# unoshield-v3.net
KiCad netlist of a schematic drawn in EAGLE
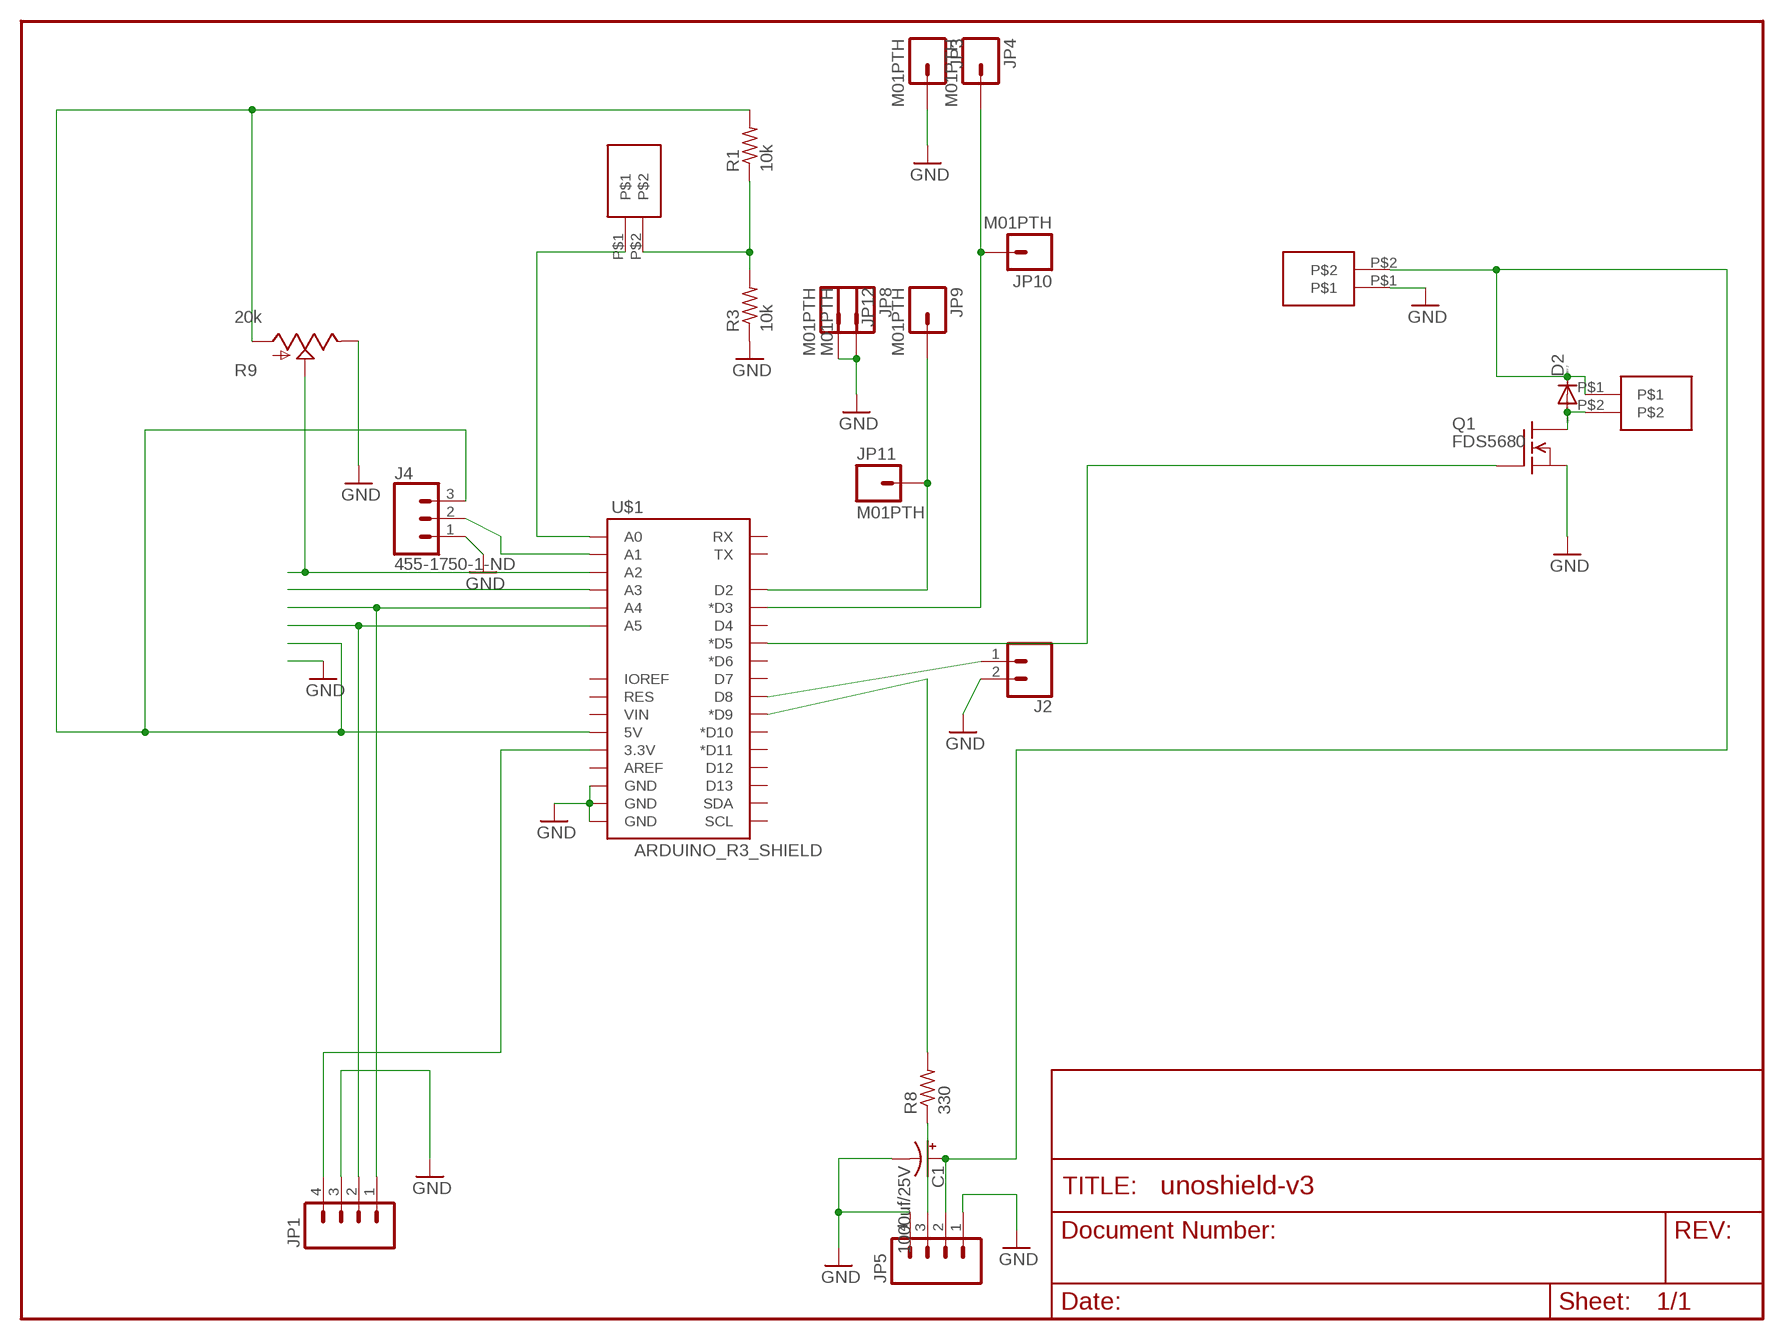
[diagram p0: schematic, sheet 1]

(export (version "E")
  (design (tool "Eeschema 10.0.6"))
  (components
    (comp (ref "C1")
      (value "1000uf/25V")
      (footprint "eagle-import:CPOL-RADIAL-1000UF-25V-KIT")
      (libsource (lib "eagle-import") (part "1000UF-25V(PTH)KIT"))
    )
    (comp (ref "D2")
      (value "DIODE-DO-214AC")
      (footprint "eagle-import:DO-214AC")
      (libsource (lib "eagle-import") (part "DIODE-DO-214AC"))
    )
    (comp (ref "J2")
      (value "CONN_02")
      (footprint "eagle-import:1X02")
      (libsource (lib "eagle-import") (part "CONN_02"))
    )
    (comp (ref "J4")
      (value "455-1750-1-ND")
      (footprint "eagle-import:1X03")
      (libsource (lib "eagle-import") (part "CONN_03"))
    )
    (comp (ref "JP1")
      (value "M04PTH")
      (footprint "eagle-import:1X04")
      (libsource (lib "eagle-import") (part "M04PTH"))
    )
    (comp (ref "JP3")
      (value "M01PTH")
      (footprint "eagle-import:1X01")
      (libsource (lib "eagle-import") (part "M01PTH"))
    )
    (comp (ref "JP4")
      (value "M01PTH")
      (footprint "eagle-import:1X01")
      (libsource (lib "eagle-import") (part "M01PTH"))
    )
    (comp (ref "JP5")
      (value "M04PTH")
      (footprint "eagle-import:1X04")
      (libsource (lib "eagle-import") (part "M04PTH"))
    )
    (comp (ref "JP8")
      (value "M01PTH")
      (footprint "eagle-import:1X01")
      (libsource (lib "eagle-import") (part "M01PTH"))
    )
    (comp (ref "JP9")
      (value "M01PTH")
      (footprint "eagle-import:1X01")
      (libsource (lib "eagle-import") (part "M01PTH"))
    )
    (comp (ref "JP10")
      (value "M01PTH")
      (footprint "eagle-import:1X01")
      (libsource (lib "eagle-import") (part "M01PTH"))
    )
    (comp (ref "JP11")
      (value "M01PTH")
      (footprint "eagle-import:1X01")
      (libsource (lib "eagle-import") (part "M01PTH"))
    )
    (comp (ref "JP12")
      (value "M01PTH")
      (footprint "eagle-import:1X01")
      (libsource (lib "eagle-import") (part "M01PTH"))
    )
    (comp (ref "Q1")
      (value "FDS5680")
      (footprint "eagle-import:SO-8")
      (libsource (lib "eagle-import") (part "FDS5680"))
    )
    (comp (ref "R1")
      (value "10k")
      (footprint "eagle-import:R0603")
      (libsource (lib "eagle-import") (part "R-US_R0603"))
    )
    (comp (ref "R3")
      (value "10k")
      (footprint "eagle-import:R0603")
      (libsource (lib "eagle-import") (part "R-US_R0603"))
    )
    (comp (ref "R8")
      (value "330")
      (footprint "eagle-import:R0603")
      (libsource (lib "eagle-import") (part "R-US_R0603"))
    )
    (comp (ref "R9")
      (value "20k")
      (footprint "eagle-import:ALPS_POT_KIT")
      (libsource (lib "eagle-import") (part "POTALPS-KIT"))
    )
    (comp (ref "U$1")
      (value "ARDUINO_R3_SHIELD")
      (footprint "eagle-import:UNO_R3_SHIELD")
      (libsource (lib "eagle-import") (part "ARDUINO_R3_SHIELD"))
    )
    (comp (ref "U$6")
      (value "SPRING-TERMINAL")
      (footprint "eagle-import:SPRING-TERMINAL")
      (libsource (lib "eagle-import") (part "SPRING-TERMINAL"))
    )
    (comp (ref "X1")
      (value "SPRING-TERMINAL")
      (footprint "eagle-import:SPRING-TERMINAL")
      (libsource (lib "eagle-import") (part "SPRING-TERMINAL"))
    )
    (comp (ref "X2")
      (value "SPRING-TERMINAL")
      (footprint "eagle-import:SPRING-TERMINAL")
      (libsource (lib "eagle-import") (part "SPRING-TERMINAL"))
    )
  )
  (nets
    (net (code "1") (name "GND") (class "Default")
      (node (ref "C1") (pin "-") (pinfunction "-_-") (pintype "passive"))
      (node (ref "J2") (pin "2") (pinfunction "2_2") (pintype "passive"))
      (node (ref "J4") (pin "1") (pinfunction "1_1") (pintype "passive"))
      (node (ref "JP1") (pin "3") (pinfunction "3_3") (pintype "passive"))
      (node (ref "JP12") (pin "1") (pinfunction "1_1") (pintype "passive"))
      (node (ref "JP3") (pin "1") (pinfunction "1_1") (pintype "passive"))
      (node (ref "JP5") (pin "1") (pinfunction "1_1") (pintype "passive"))
      (node (ref "JP5") (pin "4") (pinfunction "4_4") (pintype "passive"))
      (node (ref "JP8") (pin "1") (pinfunction "1_1") (pintype "passive"))
      (node (ref "Q1") (pin "1") (pinfunction "S_1") (pintype "passive"))
      (node (ref "Q1") (pin "2") (pinfunction "S_2") (pintype "passive"))
      (node (ref "Q1") (pin "3") (pinfunction "S_3") (pintype "passive"))
      (node (ref "R3") (pin "1") (pinfunction "1_1") (pintype "passive"))
      (node (ref "R9") (pin "P$1") (pinfunction "E_P$1") (pintype "passive"))
      (node (ref "U$1") (pin "GND@0") (pinfunction "GND_GND@0") (pintype "bidirectional"))
      (node (ref "U$1") (pin "GND@1") (pinfunction "GND_GND@1") (pintype "bidirectional"))
      (node (ref "U$1") (pin "GND@2") (pinfunction "GND_GND@2") (pintype "bidirectional"))
      (node (ref "X1") (pin "P$1") (pinfunction "P$1_P$1") (pintype "bidirectional"))
    )
    (net (code "2") (name "Net-(C1-Pad+)") (class "Default")
      (node (ref "C1") (pin "+") (pinfunction "+_+") (pintype "passive"))
      (node (ref "D2") (pin "C") (pinfunction "C_C") (pintype "passive"))
      (node (ref "JP5") (pin "2") (pinfunction "2_2") (pintype "passive"))
      (node (ref "U$6") (pin "P$1") (pinfunction "P$1_P$1") (pintype "bidirectional"))
      (node (ref "X1") (pin "P$2") (pinfunction "P$2_P$2") (pintype "bidirectional"))
    )
    (net (code "3") (name "Net-(D2-PadA)") (class "Default")
      (node (ref "D2") (pin "A") (pinfunction "A_A") (pintype "passive"))
      (node (ref "Q1") (pin "5") (pinfunction "D_5") (pintype "passive"))
      (node (ref "Q1") (pin "6") (pinfunction "D_6") (pintype "passive"))
      (node (ref "Q1") (pin "7") (pinfunction "D_7") (pintype "passive"))
      (node (ref "Q1") (pin "8") (pinfunction "D_8") (pintype "passive"))
      (node (ref "U$6") (pin "P$2") (pinfunction "P$2_P$2") (pintype "bidirectional"))
    )
    (net (code "4") (name "Net-(J2-Pad1)") (class "Default")
      (node (ref "J2") (pin "1") (pinfunction "1_1") (pintype "passive"))
      (node (ref "U$1") (pin "D8") (pinfunction "D8_D8") (pintype "bidirectional"))
    )
    (net (code "5") (name "Net-(J4-Pad2)") (class "Default")
      (node (ref "J4") (pin "2") (pinfunction "2_2") (pintype "passive"))
      (node (ref "U$1") (pin "A1") (pinfunction "A1_A1") (pintype "bidirectional"))
    )
    (net (code "6") (name "Net-(JP1-Pad1)") (class "Default")
      (node (ref "JP1") (pin "1") (pinfunction "1_1") (pintype "passive"))
      (node (ref "U$1") (pin "A4") (pinfunction "A4_A4") (pintype "bidirectional"))
    )
    (net (code "7") (name "Net-(JP1-Pad2)") (class "Default")
      (node (ref "JP1") (pin "2") (pinfunction "2_2") (pintype "passive"))
      (node (ref "U$1") (pin "A5") (pinfunction "A5_A5") (pintype "bidirectional"))
    )
    (net (code "8") (name "Net-(JP1-Pad4)") (class "Default")
      (node (ref "JP1") (pin "4") (pinfunction "4_4") (pintype "passive"))
      (node (ref "U$1") (pin "3.3V") (pinfunction "3.3V_3.3V") (pintype "bidirectional"))
    )
    (net (code "9") (name "Net-(JP5-Pad3)") (class "Default")
      (node (ref "JP5") (pin "3") (pinfunction "3_3") (pintype "passive"))
      (node (ref "R8") (pin "1") (pinfunction "1_1") (pintype "passive"))
    )
    (net (code "10") (name "Net-(JP11-Pad1)") (class "Default")
      (node (ref "JP11") (pin "1") (pinfunction "1_1") (pintype "passive"))
      (node (ref "JP9") (pin "1") (pinfunction "1_1") (pintype "passive"))
      (node (ref "U$1") (pin "D2") (pinfunction "D2_D2") (pintype "bidirectional"))
    )
    (net (code "11") (name "Net-(Q1-G)") (class "Default")
      (node (ref "Q1") (pin "4") (pinfunction "G_4") (pintype "passive"))
      (node (ref "U$1") (pin "D5") (pinfunction "*D5_D5") (pintype "bidirectional"))
    )
    (net (code "12") (name "Net-(R1-Pad1)") (class "Default")
      (node (ref "R1") (pin "1") (pinfunction "1_1") (pintype "passive"))
      (node (ref "R3") (pin "2") (pinfunction "2_2") (pintype "passive"))
      (node (ref "X2") (pin "P$2") (pinfunction "P$2_P$2") (pintype "bidirectional"))
    )
    (net (code "13") (name "Net-(R9-A)") (class "Default")
      (node (ref "J4") (pin "3") (pinfunction "3_3") (pintype "passive"))
      (node (ref "R1") (pin "2") (pinfunction "2_2") (pintype "passive"))
      (node (ref "R9") (pin "P$3") (pinfunction "A_P$3") (pintype "passive"))
      (node (ref "U$1") (pin "5V") (pinfunction "5V_5V") (pintype "bidirectional"))
    )
    (net (code "14") (name "Net-(R9-S)") (class "Default")
      (node (ref "R9") (pin "P$2") (pinfunction "S_P$2") (pintype "passive"))
      (node (ref "U$1") (pin "A2") (pinfunction "A2_A2") (pintype "bidirectional"))
    )
    (net (code "15") (name "Net-(U$1-*D3)") (class "Default")
      (node (ref "JP10") (pin "1") (pinfunction "1_1") (pintype "passive"))
      (node (ref "JP4") (pin "1") (pinfunction "1_1") (pintype "passive"))
      (node (ref "U$1") (pin "D3") (pinfunction "*D3_D3") (pintype "bidirectional"))
    )
    (net (code "16") (name "Net-(U$1-*D9)") (class "Default")
      (node (ref "R8") (pin "2") (pinfunction "2_2") (pintype "passive"))
      (node (ref "U$1") (pin "D9") (pinfunction "*D9_D9") (pintype "bidirectional"))
    )
    (net (code "17") (name "Net-(U$1-PadA0)") (class "Default")
      (node (ref "U$1") (pin "A0") (pinfunction "A0_A0") (pintype "bidirectional"))
      (node (ref "X2") (pin "P$1") (pinfunction "P$1_P$1") (pintype "bidirectional"))
    )
    (net (code "18") (name "unconnected-(U$1-*D6-PadD6)") (class "Default")
      (node (ref "U$1") (pin "D6") (pinfunction "*D6_D6") (pintype "bidirectional"))
    )
    (net (code "19") (name "unconnected-(U$1-*D10-PadD10)") (class "Default")
      (node (ref "U$1") (pin "D10") (pinfunction "*D10_D10") (pintype "bidirectional"))
    )
    (net (code "20") (name "unconnected-(U$1-*D11-PadD11)") (class "Default")
      (node (ref "U$1") (pin "D11") (pinfunction "*D11_D11") (pintype "bidirectional"))
    )
    (net (code "21") (name "unconnected-(U$1-PadA3)") (class "Default")
      (node (ref "U$1") (pin "A3") (pinfunction "A3_A3") (pintype "bidirectional"))
    )
    (net (code "22") (name "unconnected-(U$1-PadAREF)") (class "Default")
      (node (ref "U$1") (pin "AREF") (pinfunction "AREF_AREF") (pintype "bidirectional"))
    )
    (net (code "23") (name "unconnected-(U$1-PadD4)") (class "Default")
      (node (ref "U$1") (pin "D4") (pinfunction "D4_D4") (pintype "bidirectional"))
    )
    (net (code "24") (name "unconnected-(U$1-PadD7)") (class "Default")
      (node (ref "U$1") (pin "D7") (pinfunction "D7_D7") (pintype "bidirectional"))
    )
    (net (code "25") (name "unconnected-(U$1-PadD12)") (class "Default")
      (node (ref "U$1") (pin "D12") (pinfunction "D12_D12") (pintype "bidirectional"))
    )
    (net (code "26") (name "unconnected-(U$1-PadD13)") (class "Default")
      (node (ref "U$1") (pin "D13") (pinfunction "D13_D13") (pintype "bidirectional"))
    )
    (net (code "27") (name "unconnected-(U$1-PadIOREF)") (class "Default")
      (node (ref "U$1") (pin "IOREF") (pinfunction "IOREF_IOREF") (pintype "bidirectional"))
    )
    (net (code "28") (name "unconnected-(U$1-PadRES)") (class "Default")
      (node (ref "U$1") (pin "RES") (pinfunction "RES_RES") (pintype "bidirectional"))
    )
    (net (code "29") (name "unconnected-(U$1-PadRX)") (class "Default")
      (node (ref "U$1") (pin "RX") (pinfunction "RX_RX") (pintype "bidirectional"))
    )
    (net (code "30") (name "unconnected-(U$1-PadSCL)") (class "Default")
      (node (ref "U$1") (pin "SCL") (pinfunction "SCL_SCL") (pintype "bidirectional"))
    )
    (net (code "31") (name "unconnected-(U$1-PadSDA)") (class "Default")
      (node (ref "U$1") (pin "SDA") (pinfunction "SDA_SDA") (pintype "bidirectional"))
    )
    (net (code "32") (name "unconnected-(U$1-PadTX)") (class "Default")
      (node (ref "U$1") (pin "TX") (pinfunction "TX_TX") (pintype "bidirectional"))
    )
    (net (code "33") (name "unconnected-(U$1-PadVIN)") (class "Default")
      (node (ref "U$1") (pin "VIN") (pinfunction "VIN_VIN") (pintype "bidirectional"))
    )
  )
)
